# SCHEMATIC.net
KiCad netlist of a schematic drawn in Altium Designer
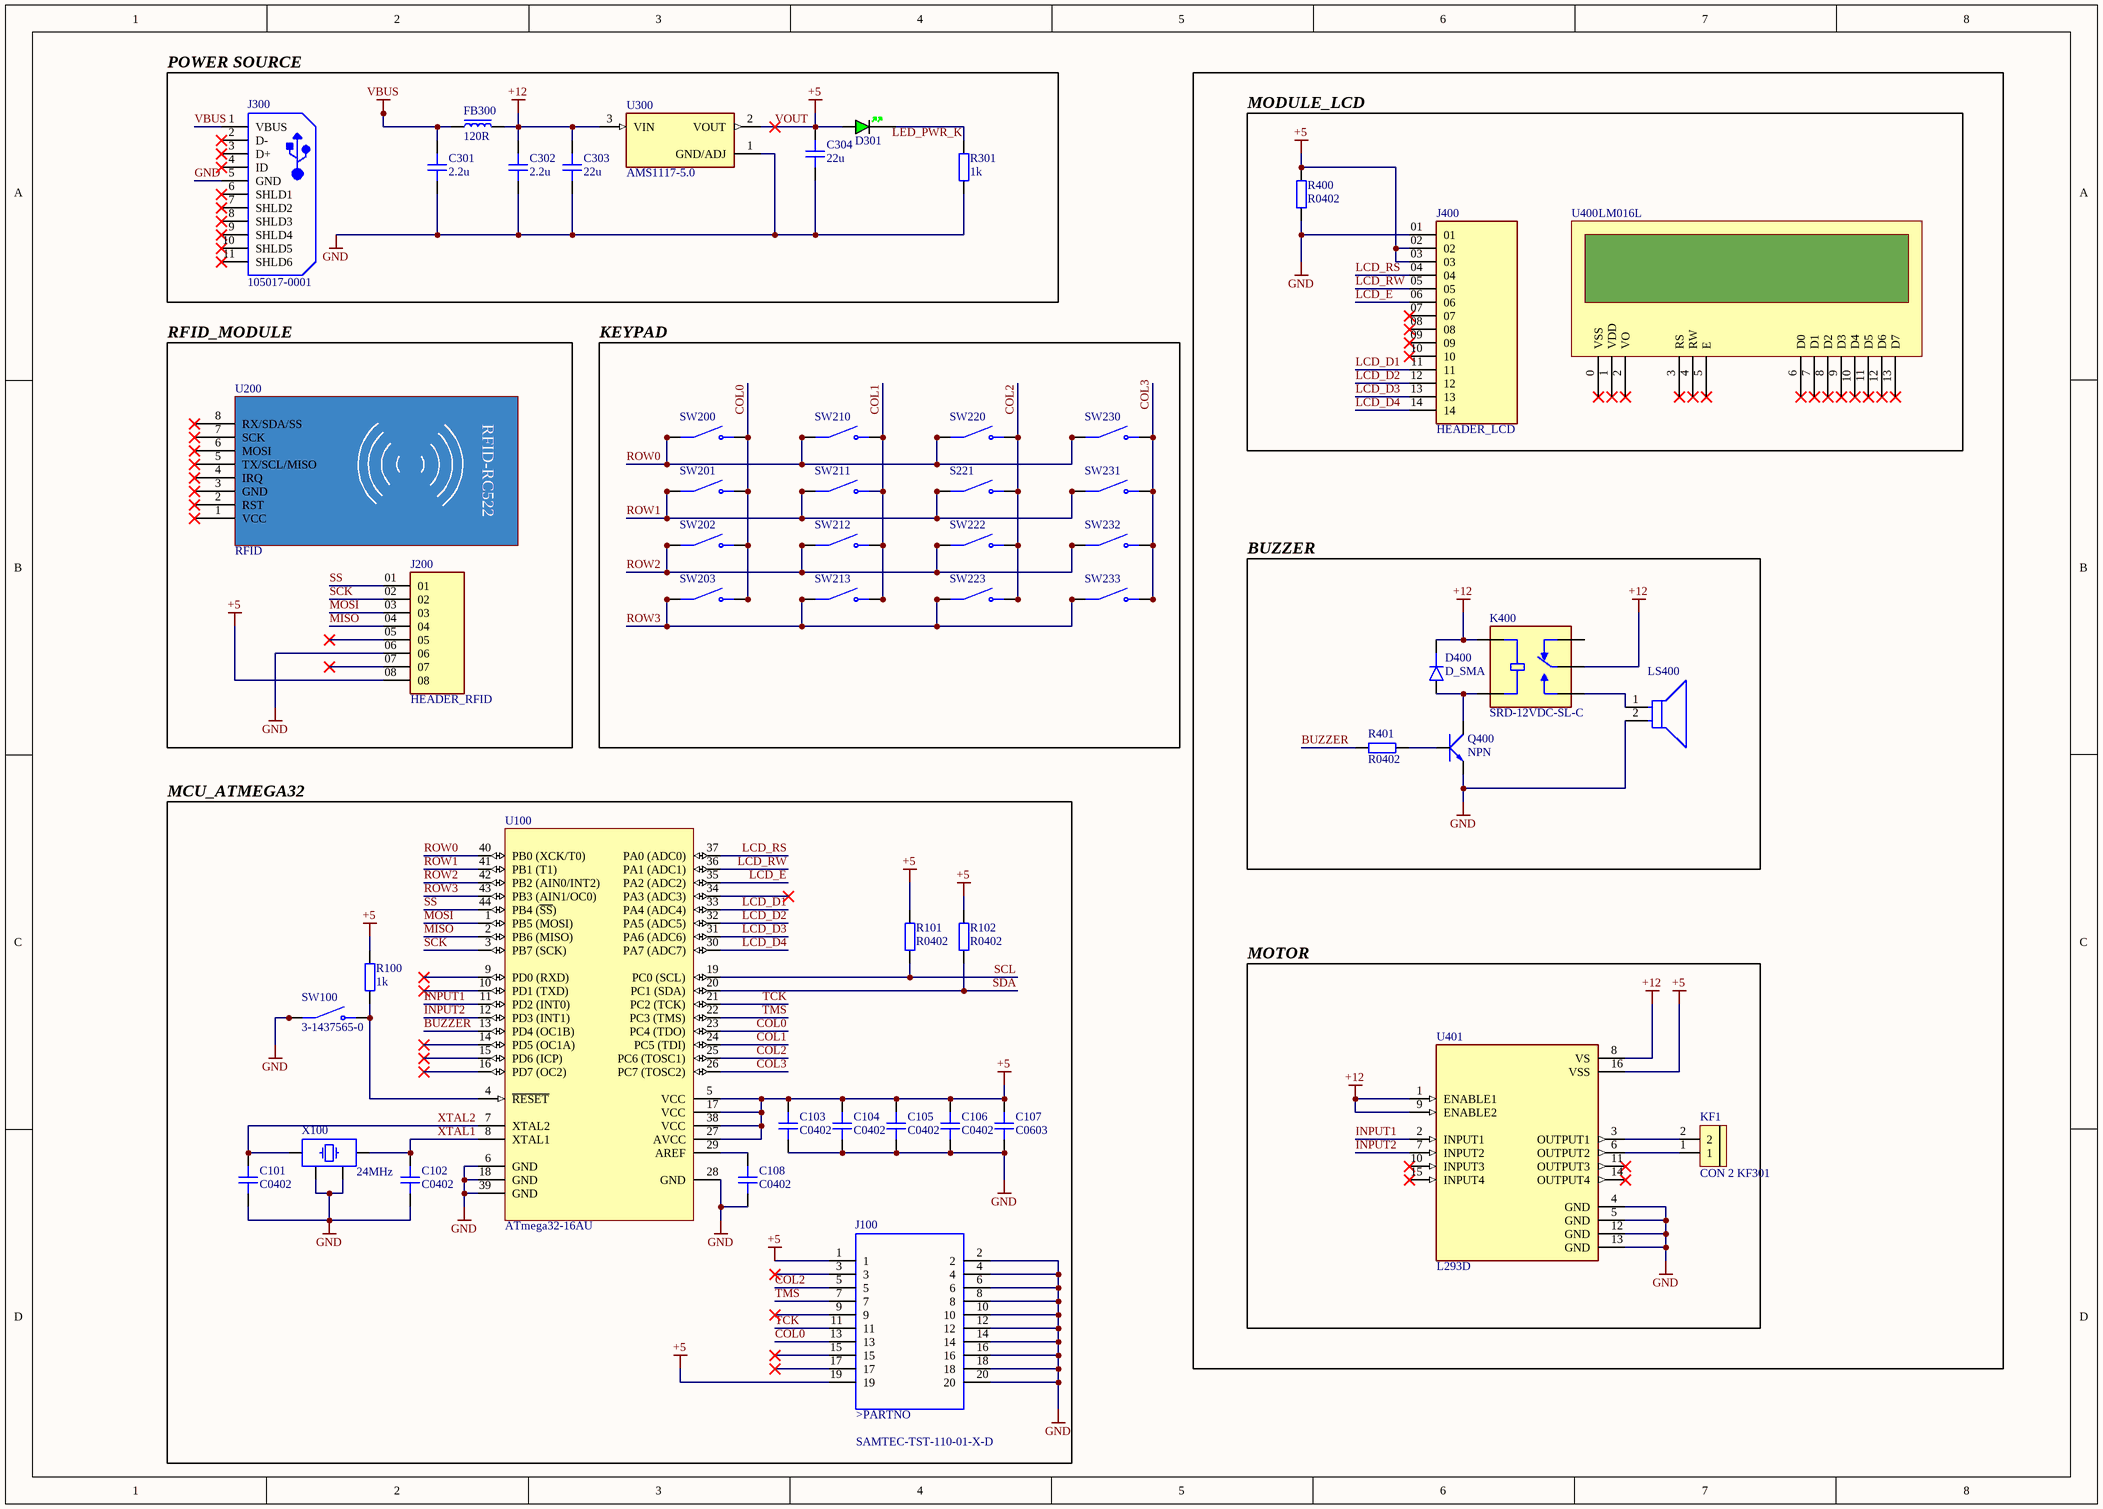
[diagram p0: SCHEMATIC.SchDoc]

(export (version "E")
  (design (tool "Eeschema 10.0.6"))
  (components
    (comp (ref "C101")
      (value "C0402")
      (footprint "CAP_0402")
      (description "Capacitor SMD 0402")
      (libsource (lib "Schematic-Lib-PhilsLab") (part "CAP_0402"))
    )
    (comp (ref "C102")
      (value "C0402")
      (footprint "CAP_0402")
      (description "Capacitor SMD 0402")
      (libsource (lib "Schematic-Lib-PhilsLab") (part "CAP_0402"))
    )
    (comp (ref "C103")
      (value "C0402")
      (footprint "CAP_0402")
      (description "Capacitor SMD 0402")
      (libsource (lib "Schematic-Lib-PhilsLab") (part "CAP_0402"))
    )
    (comp (ref "C104")
      (value "C0402")
      (footprint "CAP_0402")
      (description "Capacitor SMD 0402")
      (libsource (lib "Schematic-Lib-PhilsLab") (part "CAP_0402"))
    )
    (comp (ref "C105")
      (value "C0402")
      (footprint "CAP_0402")
      (description "Capacitor SMD 0402")
      (libsource (lib "Schematic-Lib-PhilsLab") (part "CAP_0402"))
    )
    (comp (ref "C106")
      (value "C0402")
      (footprint "CAP_0402")
      (description "Capacitor SMD 0402")
      (libsource (lib "Schematic-Lib-PhilsLab") (part "CAP_0402"))
    )
    (comp (ref "C107")
      (value "C0603")
      (footprint "CAP_0603")
      (description "Capacitor SMD 0603")
      (libsource (lib "Schematic-Lib-PhilsLab") (part "CAP_0603"))
    )
    (comp (ref "C108")
      (value "C0402")
      (footprint "CAP_0402")
      (description "Capacitor SMD 0402")
      (libsource (lib "Schematic-Lib-PhilsLab") (part "CAP_0402"))
    )
    (comp (ref "C301")
      (value "2.2u")
      (footprint "CAP_0603")
      (description "Capacitor SMD 0603")
      (libsource (lib "Schematic-Lib-PhilsLab") (part "CAP_0603"))
    )
    (comp (ref "C302")
      (value "2.2u")
      (footprint "CAP_0603")
      (description "Capacitor SMD 0603")
      (libsource (lib "Schematic-Lib-PhilsLab") (part "CAP_0603"))
    )
    (comp (ref "C303")
      (value "22u")
      (footprint "CAP_0805")
      (description "Capacitor SMD 0805")
      (libsource (lib "Schematic-Lib-PhilsLab") (part "CAP_0805"))
    )
    (comp (ref "C304")
      (value "22u")
      (footprint "CAP_0805")
      (description "Capacitor SMD 0805")
      (libsource (lib "Schematic-Lib-PhilsLab") (part "CAP_0805"))
    )
    (comp (ref "D301")
      (value "GREEN")
      (footprint "LED_0402_GREEN")
      (description "LED 0402 GREEN SMD")
      (libsource (lib "Schematic-Lib-PhilsLab") (part "LED_0402_GREEN"))
    )
    (comp (ref "D400")
      (value "D_SMA")
      (footprint "DO-214AC-2 (SMA)")
      (description "Diode SMD SMA (DO-214AA)")
      (libsource (lib "Schematic-Lib-PhilsLab") (part "D_SMA"))
    )
    (comp (ref "FB300")
      (value "120R")
      (footprint "FB_0603")
      (description "Ferrite Bead SMD 0603")
      (libsource (lib "Schematic-Lib-PhilsLab") (part "FB_0603"))
    )
    (comp (ref "J100")
      (value "~")
      (footprint "SAMTEC-TST-110-01-X-D")
      (fields (field (name "MF") "Samtec") (field (name "MP") "SAMTEC-TST-110-01-X-D"))
      (libsource (lib "SAMTEC-TST-110-01-X-D") (part "SAMTEC-TST-110-01-X-D"))
    )
    (comp (ref "J200")
      (value "HEADER_RFID")
      (footprint "SAMTEC_TSW-108-X-X-S")
      (description "Connector Header Through Hole 8 position 0.100 (2.54mm)")
      (fields (field (name "MF") "Samtec") (field (name "MP") "TSW-108-23-L-S"))
      (libsource (lib "TSW-108-X-X-S") (part "TSW-108-X-X-S"))
    )
    (comp (ref "J300")
      (value "105017-0001")
      (footprint "USB-MICRO-B_V")
      (fields (field (name "MANUFACTURER") "Molex"))
      (libsource (lib "Altium Content Vault") (part "USB-5-6SHLD"))
    )
    (comp (ref "J400")
      (value "HEADER_LCD")
      (footprint "SAMTEC_TSW-114-07-L-S")
      (description "Connector Header Through Hole 14 position 0.100 (2.54mm)")
      (fields (field (name "MF") "Samtec Inc.") (field (name "MP") "TSW-114-07-L-S"))
      (libsource (lib "TSW-114-07-L-S") (part "TSW-114-07-L-S"))
    )
    (comp (ref "K400")
      (value "SRD-12VDC-SL-C")
      (footprint "RELAY_SRD-12VDC-SL-C")
      (description "General Purpose Non Latching 12VDC SPDT Through Hole Relays RoHS")
      (libsource (lib "SRD-12VDC-SL-C (2)") (part "SRD-12VDC-SL-C"))
    )
    (comp (ref "KF1")
      (value "CON 2 KF301")
      (footprint "Con 2 KF301 5.08")
      (description "Cắm")
      (libsource (lib "Connector") (part "CON 2 KF301"))
    )
    (comp (ref "LS400")
      (value "PKB24SPCH3601-B0")
      (footprint "FP-PKB24SPCH3601-B0-MFG")
      (description "AUDIO PIEZO TRANSDUCER 3-15V TH")
      (libsource (lib "Altium Content Vault") (part "1973c4b650225fd2ddacaff6b763965"))
    )
    (comp (ref "Q400")
      (value "NPN")
      (footprint "TO92")
      (description "NPN transistor EBC")
      (libsource (lib "TranFet") (part "Trans 2N3904"))
    )
    (comp (ref "R100")
      (value "1k")
      (footprint "RES_0402")
      (description "Resistor SMD 0402")
      (libsource (lib "Schematic-Lib-PhilsLab") (part "RES_0402"))
    )
    (comp (ref "R101")
      (value "R0402")
      (footprint "RES_0402")
      (description "Resistor SMD 0402")
      (libsource (lib "Schematic-Lib-PhilsLab") (part "RES_0402"))
    )
    (comp (ref "R102")
      (value "R0402")
      (footprint "RES_0402")
      (description "Resistor SMD 0402")
      (libsource (lib "Schematic-Lib-PhilsLab") (part "RES_0402"))
    )
    (comp (ref "R301")
      (value "1k")
      (footprint "RES_0402")
      (description "Resistor SMD 0402")
      (libsource (lib "Schematic-Lib-PhilsLab") (part "RES_0402"))
    )
    (comp (ref "R400")
      (value "R0402")
      (footprint "RES_0402")
      (description "Resistor SMD 0402")
      (libsource (lib "Schematic-Lib-PhilsLab") (part "RES_0402"))
    )
    (comp (ref "R401")
      (value "R0402")
      (footprint "RES_0402")
      (description "Resistor SMD 0402")
      (libsource (lib "Schematic-Lib-PhilsLab") (part "RES_0402"))
    )
    (comp (ref "S221")
      (value "3-1437565-0")
      (footprint "SW_3-1437565-0")
      (description "Switch Tactile OFF (ON) SPST Round Button Gull Wing 0.05A 24VDC 1VA 9.18N SMD T/R")
      (fields (field (name "MF") "TE Connectivity"))
      (libsource (lib "3-1437565-0") (part "3-1437565-0"))
    )
    (comp (ref "SW100")
      (value "3-1437565-0")
      (footprint "SW_3-1437565-0")
      (description "Switch Tactile OFF (ON) SPST Round Button Gull Wing 0.05A 24VDC 1VA 9.18N SMD T/R")
      (fields (field (name "MF") "TE Connectivity"))
      (libsource (lib "3-1437565-0") (part "3-1437565-0"))
    )
    (comp (ref "SW200")
      (value "3-1437565-0")
      (footprint "SW_3-1437565-0")
      (description "Switch Tactile OFF (ON) SPST Round Button Gull Wing 0.05A 24VDC 1VA 9.18N SMD T/R")
      (fields (field (name "MF") "TE Connectivity"))
      (libsource (lib "3-1437565-0") (part "3-1437565-0"))
    )
    (comp (ref "SW201")
      (value "3-1437565-0")
      (footprint "SW_3-1437565-0")
      (description "Switch Tactile OFF (ON) SPST Round Button Gull Wing 0.05A 24VDC 1VA 9.18N SMD T/R")
      (fields (field (name "MF") "TE Connectivity"))
      (libsource (lib "3-1437565-0") (part "3-1437565-0"))
    )
    (comp (ref "SW202")
      (value "3-1437565-0")
      (footprint "SW_3-1437565-0")
      (description "Switch Tactile OFF (ON) SPST Round Button Gull Wing 0.05A 24VDC 1VA 9.18N SMD T/R")
      (fields (field (name "MF") "TE Connectivity"))
      (libsource (lib "3-1437565-0") (part "3-1437565-0"))
    )
    (comp (ref "SW203")
      (value "3-1437565-0")
      (footprint "SW_3-1437565-0")
      (description "Switch Tactile OFF (ON) SPST Round Button Gull Wing 0.05A 24VDC 1VA 9.18N SMD T/R")
      (fields (field (name "MF") "TE Connectivity"))
      (libsource (lib "3-1437565-0") (part "3-1437565-0"))
    )
    (comp (ref "SW210")
      (value "3-1437565-0")
      (footprint "SW_3-1437565-0")
      (description "Switch Tactile OFF (ON) SPST Round Button Gull Wing 0.05A 24VDC 1VA 9.18N SMD T/R")
      (fields (field (name "MF") "TE Connectivity"))
      (libsource (lib "3-1437565-0") (part "3-1437565-0"))
    )
    (comp (ref "SW211")
      (value "3-1437565-0")
      (footprint "SW_3-1437565-0")
      (description "Switch Tactile OFF (ON) SPST Round Button Gull Wing 0.05A 24VDC 1VA 9.18N SMD T/R")
      (fields (field (name "MF") "TE Connectivity"))
      (libsource (lib "3-1437565-0") (part "3-1437565-0"))
    )
    (comp (ref "SW212")
      (value "3-1437565-0")
      (footprint "SW_3-1437565-0")
      (description "Switch Tactile OFF (ON) SPST Round Button Gull Wing 0.05A 24VDC 1VA 9.18N SMD T/R")
      (fields (field (name "MF") "TE Connectivity"))
      (libsource (lib "3-1437565-0") (part "3-1437565-0"))
    )
    (comp (ref "SW213")
      (value "3-1437565-0")
      (footprint "SW_3-1437565-0")
      (description "Switch Tactile OFF (ON) SPST Round Button Gull Wing 0.05A 24VDC 1VA 9.18N SMD T/R")
      (fields (field (name "MF") "TE Connectivity"))
      (libsource (lib "3-1437565-0") (part "3-1437565-0"))
    )
    (comp (ref "SW220")
      (value "3-1437565-0")
      (footprint "SW_3-1437565-0")
      (description "Switch Tactile OFF (ON) SPST Round Button Gull Wing 0.05A 24VDC 1VA 9.18N SMD T/R")
      (fields (field (name "MF") "TE Connectivity"))
      (libsource (lib "3-1437565-0") (part "3-1437565-0"))
    )
    (comp (ref "SW222")
      (value "3-1437565-0")
      (footprint "SW_3-1437565-0")
      (description "Switch Tactile OFF (ON) SPST Round Button Gull Wing 0.05A 24VDC 1VA 9.18N SMD T/R")
      (fields (field (name "MF") "TE Connectivity"))
      (libsource (lib "3-1437565-0") (part "3-1437565-0"))
    )
    (comp (ref "SW223")
      (value "3-1437565-0")
      (footprint "SW_3-1437565-0")
      (description "Switch Tactile OFF (ON) SPST Round Button Gull Wing 0.05A 24VDC 1VA 9.18N SMD T/R")
      (fields (field (name "MF") "TE Connectivity"))
      (libsource (lib "3-1437565-0") (part "3-1437565-0"))
    )
    (comp (ref "SW230")
      (value "3-1437565-0")
      (footprint "SW_3-1437565-0")
      (description "Switch Tactile OFF (ON) SPST Round Button Gull Wing 0.05A 24VDC 1VA 9.18N SMD T/R")
      (fields (field (name "MF") "TE Connectivity"))
      (libsource (lib "3-1437565-0") (part "3-1437565-0"))
    )
    (comp (ref "SW231")
      (value "3-1437565-0")
      (footprint "SW_3-1437565-0")
      (description "Switch Tactile OFF (ON) SPST Round Button Gull Wing 0.05A 24VDC 1VA 9.18N SMD T/R")
      (fields (field (name "MF") "TE Connectivity"))
      (libsource (lib "3-1437565-0") (part "3-1437565-0"))
    )
    (comp (ref "SW232")
      (value "3-1437565-0")
      (footprint "SW_3-1437565-0")
      (description "Switch Tactile OFF (ON) SPST Round Button Gull Wing 0.05A 24VDC 1VA 9.18N SMD T/R")
      (fields (field (name "MF") "TE Connectivity"))
      (libsource (lib "3-1437565-0") (part "3-1437565-0"))
    )
    (comp (ref "SW233")
      (value "3-1437565-0")
      (footprint "SW_3-1437565-0")
      (description "Switch Tactile OFF (ON) SPST Round Button Gull Wing 0.05A 24VDC 1VA 9.18N SMD T/R")
      (fields (field (name "MF") "TE Connectivity"))
      (libsource (lib "3-1437565-0") (part "3-1437565-0"))
    )
    (comp (ref "U100")
      (value "ATmega32-16AU")
      (footprint "44A_N")
      (libsource (lib "Altium Content Vault") (part "MC-8B-ATM32-SQ44"))
    )
    (comp (ref "U200") (value "RFID") (libsource (lib "RC522") (part "Component_1")))
    (comp (ref "U300")
      (value "AMS1117-5.0")
      (footprint "SOT229P700X180-4N")
      (description "1A LOW DROPOUT VOLTAGE REGULATOR")
      (fields (field (name "MF") "ams"))
      (libsource (lib "AMS1117-5.0") (part "AMS1117-5.0"))
    )
    (comp (ref "U400") (value "LM016L") (libsource (lib "LM016L") (part "LM016L")))
    (comp (ref "U401")
      (value "L293D")
      (footprint "DIP880W50P254L2000H510Q16")
      (description "Bipolar Motor Driver - Parallel 16-PowerDIP")
      (fields (field (name "MF") "STMicroelectronics"))
      (libsource (lib "L293D") (part "L293D"))
    )
    (comp (ref "X100")
      (value "24MHz")
      (footprint "XTAL_3225")
      (description "Crystal SMD 24MHz 10PPM 7pF 3225")
      (fields
        (field (name "MANUFACTURER") "Epson")
        (field (name "MANUFACTURER PART NUMBER") "TSX-3225 24.0000MF15X-AC")
      )
      (libsource (lib "Schematic-Lib-PhilsLab") (part "TSX-3225_24.0000MF15X-AC"))
    )
  )
  (nets
    (net (code "1") (name "+5") (class "Default")
      (node (ref "C103") (pin "2") (pinfunction "2_2") (pintype "passive"))
      (node (ref "C104") (pin "2") (pinfunction "2_2") (pintype "passive"))
      (node (ref "C105") (pin "2") (pinfunction "2_2") (pintype "passive"))
      (node (ref "C106") (pin "2") (pinfunction "2_2") (pintype "passive"))
      (node (ref "C107") (pin "2") (pinfunction "2_2") (pintype "passive"))
      (node (ref "C304") (pin "2") (pinfunction "2_2") (pintype "passive"))
      (node (ref "D301") (pin "A") (pinfunction "A_A") (pintype "passive"))
      (node (ref "J100") (pin "1") (pinfunction "1_1") (pintype "passive"))
      (node (ref "J100") (pin "19") (pinfunction "19_19") (pintype "passive"))
      (node (ref "J200") (pin "08") (pinfunction "08_08") (pintype "passive"))
      (node (ref "J400") (pin "02") (pinfunction "02_02") (pintype "passive"))
      (node (ref "J400") (pin "03") (pinfunction "03_03") (pintype "passive"))
      (node (ref "R100") (pin "2") (pinfunction "2_2") (pintype "passive"))
      (node (ref "R101") (pin "2") (pinfunction "2_2") (pintype "passive"))
      (node (ref "R102") (pin "2") (pinfunction "2_2") (pintype "passive"))
      (node (ref "R400") (pin "2") (pinfunction "2_2") (pintype "passive"))
      (node (ref "U100") (pin "17") (pinfunction "VCC_17") (pintype "power_in"))
      (node (ref "U100") (pin "27") (pinfunction "AVCC_27") (pintype "power_in"))
      (node (ref "U100") (pin "38") (pinfunction "VCC_38") (pintype "power_in"))
      (node (ref "U100") (pin "5") (pinfunction "VCC_5") (pintype "power_in"))
      (node (ref "U300") (pin "2") (pinfunction "VOUT_2") (pintype "output"))
      (node (ref "U401") (pin "16") (pinfunction "VSS_16") (pintype "power_in"))
    )
    (net (code "2") (name "+12") (class "Default")
      (node (ref "C302") (pin "2") (pinfunction "2_2") (pintype "passive"))
      (node (ref "C303") (pin "2") (pinfunction "2_2") (pintype "passive"))
      (node (ref "D400") (pin "K") (pinfunction "K_K") (pintype "passive"))
      (node (ref "FB300") (pin "2") (pinfunction "2_2") (pintype "passive"))
      (node (ref "K400") (pin "COIL1") (pinfunction "COIL1_COIL1") (pintype "passive"))
      (node (ref "K400") (pin "COM") (pinfunction "COM_COM") (pintype "passive"))
      (node (ref "U300") (pin "3") (pinfunction "VIN_3") (pintype "input"))
      (node (ref "U401") (pin "1") (pinfunction "ENABLE1_1") (pintype "input"))
      (node (ref "U401") (pin "8") (pinfunction "VS_8") (pintype "power_in"))
      (node (ref "U401") (pin "9") (pinfunction "ENABLE2_9") (pintype "input"))
    )
    (net (code "3") (name "/BUZZER") (class "Default")
      (node (ref "R401") (pin "1") (pinfunction "1_1") (pintype "passive"))
      (node (ref "U100") (pin "13") (pinfunction "PD4_(OC1B)_13") (pintype "bidirectional"))
    )
    (net (code "4") (name "/COL0") (class "Default")
      (node (ref "J100") (pin "13") (pinfunction "13_13") (pintype "passive"))
      (node (ref "SW200") (pin "3") (pinfunction "NO_3") (pintype "passive"))
      (node (ref "SW200") (pin "4") (pinfunction "NO_4") (pintype "passive"))
      (node (ref "SW201") (pin "3") (pinfunction "NO_3") (pintype "passive"))
      (node (ref "SW201") (pin "4") (pinfunction "NO_4") (pintype "passive"))
      (node (ref "SW202") (pin "3") (pinfunction "NO_3") (pintype "passive"))
      (node (ref "SW202") (pin "4") (pinfunction "NO_4") (pintype "passive"))
      (node (ref "SW203") (pin "3") (pinfunction "NO_3") (pintype "passive"))
      (node (ref "SW203") (pin "4") (pinfunction "NO_4") (pintype "passive"))
      (node (ref "U100") (pin "23") (pinfunction "PC4_(TDO)_23") (pintype "bidirectional"))
    )
    (net (code "5") (name "/COL1") (class "Default")
      (node (ref "SW210") (pin "3") (pinfunction "NO_3") (pintype "passive"))
      (node (ref "SW210") (pin "4") (pinfunction "NO_4") (pintype "passive"))
      (node (ref "SW211") (pin "3") (pinfunction "NO_3") (pintype "passive"))
      (node (ref "SW211") (pin "4") (pinfunction "NO_4") (pintype "passive"))
      (node (ref "SW212") (pin "3") (pinfunction "NO_3") (pintype "passive"))
      (node (ref "SW212") (pin "4") (pinfunction "NO_4") (pintype "passive"))
      (node (ref "SW213") (pin "3") (pinfunction "NO_3") (pintype "passive"))
      (node (ref "SW213") (pin "4") (pinfunction "NO_4") (pintype "passive"))
      (node (ref "U100") (pin "24") (pinfunction "PC5_(TDI)_24") (pintype "bidirectional"))
    )
    (net (code "6") (name "/COL2") (class "Default")
      (node (ref "J100") (pin "5") (pinfunction "5_5") (pintype "passive"))
      (node (ref "S221") (pin "3") (pinfunction "NO_3") (pintype "passive"))
      (node (ref "S221") (pin "4") (pinfunction "NO_4") (pintype "passive"))
      (node (ref "SW220") (pin "3") (pinfunction "NO_3") (pintype "passive"))
      (node (ref "SW220") (pin "4") (pinfunction "NO_4") (pintype "passive"))
      (node (ref "SW222") (pin "3") (pinfunction "NO_3") (pintype "passive"))
      (node (ref "SW222") (pin "4") (pinfunction "NO_4") (pintype "passive"))
      (node (ref "SW223") (pin "3") (pinfunction "NO_3") (pintype "passive"))
      (node (ref "SW223") (pin "4") (pinfunction "NO_4") (pintype "passive"))
      (node (ref "U100") (pin "25") (pinfunction "PC6_(TOSC1)_25") (pintype "bidirectional"))
    )
    (net (code "7") (name "/COL3") (class "Default")
      (node (ref "SW230") (pin "3") (pinfunction "NO_3") (pintype "passive"))
      (node (ref "SW230") (pin "4") (pinfunction "NO_4") (pintype "passive"))
      (node (ref "SW231") (pin "3") (pinfunction "NO_3") (pintype "passive"))
      (node (ref "SW231") (pin "4") (pinfunction "NO_4") (pintype "passive"))
      (node (ref "SW232") (pin "3") (pinfunction "NO_3") (pintype "passive"))
      (node (ref "SW232") (pin "4") (pinfunction "NO_4") (pintype "passive"))
      (node (ref "SW233") (pin "3") (pinfunction "NO_3") (pintype "passive"))
      (node (ref "SW233") (pin "4") (pinfunction "NO_4") (pintype "passive"))
      (node (ref "U100") (pin "26") (pinfunction "PC7_(TOSC2)_26") (pintype "bidirectional"))
    )
    (net (code "8") (name "/INPUT1") (class "Default")
      (node (ref "U100") (pin "11") (pinfunction "PD2_(INT0)_11") (pintype "bidirectional"))
      (node (ref "U401") (pin "2") (pinfunction "INPUT1_2") (pintype "input"))
    )
    (net (code "9") (name "/INPUT2") (class "Default")
      (node (ref "U100") (pin "12") (pinfunction "PD3_(INT1)_12") (pintype "bidirectional"))
      (node (ref "U401") (pin "7") (pinfunction "INPUT2_7") (pintype "input"))
    )
    (net (code "10") (name "/LCD_D1") (class "Default")
      (node (ref "J400") (pin "11") (pinfunction "11_11") (pintype "passive"))
      (node (ref "U100") (pin "33") (pinfunction "PA4_(ADC4)_33") (pintype "bidirectional"))
    )
    (net (code "11") (name "/LCD_D2") (class "Default")
      (node (ref "J400") (pin "12") (pinfunction "12_12") (pintype "passive"))
      (node (ref "U100") (pin "32") (pinfunction "PA5_(ADC5)_32") (pintype "bidirectional"))
    )
    (net (code "12") (name "/LCD_D3") (class "Default")
      (node (ref "J400") (pin "13") (pinfunction "13_13") (pintype "passive"))
      (node (ref "U100") (pin "31") (pinfunction "PA6_(ADC6)_31") (pintype "bidirectional"))
    )
    (net (code "13") (name "/LCD_D4") (class "Default")
      (node (ref "J400") (pin "14") (pinfunction "14_14") (pintype "passive"))
      (node (ref "U100") (pin "30") (pinfunction "PA7_(ADC7)_30") (pintype "bidirectional"))
    )
    (net (code "14") (name "/LCD_E") (class "Default")
      (node (ref "J400") (pin "06") (pinfunction "06_06") (pintype "passive"))
      (node (ref "U100") (pin "35") (pinfunction "PA2_(ADC2)_35") (pintype "bidirectional"))
    )
    (net (code "15") (name "/LCD_RS") (class "Default")
      (node (ref "J400") (pin "04") (pinfunction "04_04") (pintype "passive"))
      (node (ref "U100") (pin "37") (pinfunction "PA0_(ADC0)_37") (pintype "bidirectional"))
    )
    (net (code "16") (name "/LCD_RW") (class "Default")
      (node (ref "J400") (pin "05") (pinfunction "05_05") (pintype "passive"))
      (node (ref "U100") (pin "36") (pinfunction "PA1_(ADC1)_36") (pintype "bidirectional"))
    )
    (net (code "17") (name "/LED_PWR_K") (class "Default")
      (node (ref "D301") (pin "K") (pinfunction "K_K") (pintype "passive"))
      (node (ref "R301") (pin "2") (pinfunction "2_2") (pintype "passive"))
    )
    (net (code "18") (name "/MISO") (class "Default")
      (node (ref "J200") (pin "04") (pinfunction "04_04") (pintype "passive"))
      (node (ref "U100") (pin "2") (pinfunction "PB6_(MISO)_2") (pintype "bidirectional"))
    )
    (net (code "19") (name "/MOSI") (class "Default")
      (node (ref "J200") (pin "03") (pinfunction "03_03") (pintype "passive"))
      (node (ref "U100") (pin "1") (pinfunction "PB5_(MOSI)_1") (pintype "bidirectional"))
    )
    (net (code "20") (name "/ROW0") (class "Default")
      (node (ref "SW200") (pin "1") (pinfunction "COM_1") (pintype "passive"))
      (node (ref "SW200") (pin "2") (pinfunction "COM_2") (pintype "passive"))
      (node (ref "SW210") (pin "1") (pinfunction "COM_1") (pintype "passive"))
      (node (ref "SW210") (pin "2") (pinfunction "COM_2") (pintype "passive"))
      (node (ref "SW220") (pin "1") (pinfunction "COM_1") (pintype "passive"))
      (node (ref "SW220") (pin "2") (pinfunction "COM_2") (pintype "passive"))
      (node (ref "SW230") (pin "1") (pinfunction "COM_1") (pintype "passive"))
      (node (ref "SW230") (pin "2") (pinfunction "COM_2") (pintype "passive"))
      (node (ref "U100") (pin "40") (pinfunction "PB0_(XCK/T0)_40") (pintype "bidirectional"))
    )
    (net (code "21") (name "/ROW1") (class "Default")
      (node (ref "S221") (pin "1") (pinfunction "COM_1") (pintype "passive"))
      (node (ref "S221") (pin "2") (pinfunction "COM_2") (pintype "passive"))
      (node (ref "SW201") (pin "1") (pinfunction "COM_1") (pintype "passive"))
      (node (ref "SW201") (pin "2") (pinfunction "COM_2") (pintype "passive"))
      (node (ref "SW211") (pin "1") (pinfunction "COM_1") (pintype "passive"))
      (node (ref "SW211") (pin "2") (pinfunction "COM_2") (pintype "passive"))
      (node (ref "SW231") (pin "1") (pinfunction "COM_1") (pintype "passive"))
      (node (ref "SW231") (pin "2") (pinfunction "COM_2") (pintype "passive"))
      (node (ref "U100") (pin "41") (pinfunction "PB1_(T1)_41") (pintype "bidirectional"))
    )
    (net (code "22") (name "/ROW2") (class "Default")
      (node (ref "SW202") (pin "1") (pinfunction "COM_1") (pintype "passive"))
      (node (ref "SW202") (pin "2") (pinfunction "COM_2") (pintype "passive"))
      (node (ref "SW212") (pin "1") (pinfunction "COM_1") (pintype "passive"))
      (node (ref "SW212") (pin "2") (pinfunction "COM_2") (pintype "passive"))
      (node (ref "SW222") (pin "1") (pinfunction "COM_1") (pintype "passive"))
      (node (ref "SW222") (pin "2") (pinfunction "COM_2") (pintype "passive"))
      (node (ref "SW232") (pin "1") (pinfunction "COM_1") (pintype "passive"))
      (node (ref "SW232") (pin "2") (pinfunction "COM_2") (pintype "passive"))
      (node (ref "U100") (pin "42") (pinfunction "PB2_(AIN0/INT2)_42") (pintype "bidirectional"))
    )
    (net (code "23") (name "/ROW3") (class "Default")
      (node (ref "SW203") (pin "1") (pinfunction "COM_1") (pintype "passive"))
      (node (ref "SW203") (pin "2") (pinfunction "COM_2") (pintype "passive"))
      (node (ref "SW213") (pin "1") (pinfunction "COM_1") (pintype "passive"))
      (node (ref "SW213") (pin "2") (pinfunction "COM_2") (pintype "passive"))
      (node (ref "SW223") (pin "1") (pinfunction "COM_1") (pintype "passive"))
      (node (ref "SW223") (pin "2") (pinfunction "COM_2") (pintype "passive"))
      (node (ref "SW233") (pin "1") (pinfunction "COM_1") (pintype "passive"))
      (node (ref "SW233") (pin "2") (pinfunction "COM_2") (pintype "passive"))
      (node (ref "U100") (pin "43") (pinfunction "PB3_(AIN1/OC0)_43") (pintype "bidirectional"))
    )
    (net (code "24") (name "/SCK") (class "Default")
      (node (ref "J200") (pin "02") (pinfunction "02_02") (pintype "passive"))
      (node (ref "U100") (pin "3") (pinfunction "PB7_(SCK)_3") (pintype "bidirectional"))
    )
    (net (code "25") (name "/SCL") (class "Default")
      (node (ref "R101") (pin "1") (pinfunction "1_1") (pintype "passive"))
      (node (ref "U100") (pin "19") (pinfunction "PC0_(SCL)_19") (pintype "bidirectional"))
    )
    (net (code "26") (name "/SDA") (class "Default")
      (node (ref "R102") (pin "1") (pinfunction "1_1") (pintype "passive"))
      (node (ref "U100") (pin "20") (pinfunction "PC1_(SDA)_20") (pintype "bidirectional"))
    )
    (net (code "27") (name "/SS") (class "Default")
      (node (ref "J200") (pin "01") (pinfunction "01_01") (pintype "passive"))
      (node (ref "U100") (pin "44") (pinfunction "PB4_(~{SS})_44") (pintype "bidirectional"))
    )
    (net (code "28") (name "/TCK") (class "Default")
      (node (ref "J100") (pin "11") (pinfunction "11_11") (pintype "passive"))
      (node (ref "U100") (pin "21") (pinfunction "PC2_(TCK)_21") (pintype "bidirectional"))
    )
    (net (code "29") (name "/TMS") (class "Default")
      (node (ref "J100") (pin "7") (pinfunction "7_7") (pintype "passive"))
      (node (ref "U100") (pin "22") (pinfunction "PC3_(TMS)_22") (pintype "bidirectional"))
    )
    (net (code "31") (name "/XTAL1") (class "Default")
      (node (ref "C102") (pin "2") (pinfunction "2_2") (pintype "passive"))
      (node (ref "U100") (pin "8") (pinfunction "XTAL1_8") (pintype "passive"))
      (node (ref "X100") (pin "3") (pinfunction "3_3") (pintype "passive"))
    )
    (net (code "32") (name "/XTAL2") (class "Default")
      (node (ref "C101") (pin "2") (pinfunction "2_2") (pintype "passive"))
      (node (ref "U100") (pin "7") (pinfunction "XTAL2_7") (pintype "passive"))
      (node (ref "X100") (pin "1") (pinfunction "1_1") (pintype "passive"))
    )
    (net (code "33") (name "GND") (class "Default")
      (node (ref "C101") (pin "1") (pinfunction "1_1") (pintype "passive"))
      (node (ref "C102") (pin "1") (pinfunction "1_1") (pintype "passive"))
      (node (ref "C103") (pin "1") (pinfunction "1_1") (pintype "passive"))
      (node (ref "C104") (pin "1") (pinfunction "1_1") (pintype "passive"))
      (node (ref "C105") (pin "1") (pinfunction "1_1") (pintype "passive"))
      (node (ref "C106") (pin "1") (pinfunction "1_1") (pintype "passive"))
      (node (ref "C107") (pin "1") (pinfunction "1_1") (pintype "passive"))
      (node (ref "C108") (pin "1") (pinfunction "1_1") (pintype "passive"))
      (node (ref "C301") (pin "1") (pinfunction "1_1") (pintype "passive"))
      (node (ref "C302") (pin "1") (pinfunction "1_1") (pintype "passive"))
      (node (ref "C303") (pin "1") (pinfunction "1_1") (pintype "passive"))
      (node (ref "C304") (pin "1") (pinfunction "1_1") (pintype "passive"))
      (node (ref "J100") (pin "10") (pinfunction "10_10") (pintype "passive"))
      (node (ref "J100") (pin "12") (pinfunction "12_12") (pintype "passive"))
      (node (ref "J100") (pin "14") (pinfunction "14_14") (pintype "passive"))
      (node (ref "J100") (pin "16") (pinfunction "16_16") (pintype "passive"))
      (node (ref "J100") (pin "18") (pinfunction "18_18") (pintype "passive"))
      (node (ref "J100") (pin "2") (pinfunction "2_2") (pintype "passive"))
      (node (ref "J100") (pin "20") (pinfunction "20_20") (pintype "passive"))
      (node (ref "J100") (pin "4") (pinfunction "4_4") (pintype "passive"))
      (node (ref "J100") (pin "6") (pinfunction "6_6") (pintype "passive"))
      (node (ref "J100") (pin "8") (pinfunction "8_8") (pintype "passive"))
      (node (ref "J200") (pin "06") (pinfunction "06_06") (pintype "passive"))
      (node (ref "J300") (pin "5") (pinfunction "GND_5") (pintype "passive"))
      (node (ref "J400") (pin "01") (pinfunction "01_01") (pintype "passive"))
      (node (ref "LS400") (pin "2") (pinfunction "A_2") (pintype "passive"))
      (node (ref "Q400") (pin "1") (pinfunction "E_1") (pintype "passive"))
      (node (ref "R301") (pin "1") (pinfunction "1_1") (pintype "passive"))
      (node (ref "R400") (pin "1") (pinfunction "1_1") (pintype "passive"))
      (node (ref "SW100") (pin "1") (pinfunction "COM_1") (pintype "passive"))
      (node (ref "SW100") (pin "2") (pinfunction "COM_2") (pintype "passive"))
      (node (ref "U100") (pin "18") (pinfunction "GND_18") (pintype "power_in"))
      (node (ref "U100") (pin "28") (pinfunction "GND_28") (pintype "power_in"))
      (node (ref "U100") (pin "39") (pinfunction "GND_39") (pintype "power_in"))
      (node (ref "U100") (pin "6") (pinfunction "GND_6") (pintype "power_in"))
      (node (ref "U300") (pin "1") (pinfunction "GND/ADJ_1") (pintype "power_in"))
      (node (ref "U401") (pin "12") (pinfunction "GND_12") (pintype "power_in"))
      (node (ref "U401") (pin "13") (pinfunction "GND_13") (pintype "power_in"))
      (node (ref "U401") (pin "4") (pinfunction "GND_4") (pintype "power_in"))
      (node (ref "U401") (pin "5") (pinfunction "GND_5") (pintype "power_in"))
      (node (ref "X100") (pin "2") (pinfunction "2_2") (pintype "passive"))
      (node (ref "X100") (pin "4") (pinfunction "4_4") (pintype "passive"))
    )
    (net (code "34") (name "Net-(LS400-C)") (class "Default")
      (node (ref "K400") (pin "NO") (pinfunction "NO_NO") (pintype "passive"))
      (node (ref "LS400") (pin "1") (pinfunction "C_1") (pintype "passive"))
    )
    (net (code "35") (name "Net-(Q400-B)") (class "Default")
      (node (ref "Q400") (pin "2") (pinfunction "B_2") (pintype "passive"))
      (node (ref "R401") (pin "2") (pinfunction "2_2") (pintype "passive"))
    )
    (net (code "36") (name "Net-(Q400-C)") (class "Default")
      (node (ref "D400") (pin "A") (pinfunction "A_A") (pintype "passive"))
      (node (ref "K400") (pin "COIL2") (pinfunction "COIL2_COIL2") (pintype "passive"))
      (node (ref "Q400") (pin "3") (pinfunction "C_3") (pintype "passive"))
    )
    (net (code "37") (name "Net-(U100-AREF)") (class "Default")
      (node (ref "C108") (pin "2") (pinfunction "2_2") (pintype "passive"))
      (node (ref "U100") (pin "29") (pinfunction "AREF_29") (pintype "passive"))
    )
    (net (code "38") (name "Net-(U100-~{RESET})") (class "Default")
      (node (ref "R100") (pin "1") (pinfunction "1_1") (pintype "passive"))
      (node (ref "SW100") (pin "3") (pinfunction "NO_3") (pintype "passive"))
      (node (ref "SW100") (pin "4") (pinfunction "NO_4") (pintype "passive"))
      (node (ref "U100") (pin "4") (pinfunction "~{RESET}_4") (pintype "input"))
    )
    (net (code "39") (name "Net-(U401-OUTPUT1)") (class "Default")
      (node (ref "KF1") (pin "2") (pinfunction "2_2") (pintype "passive"))
      (node (ref "U401") (pin "3") (pinfunction "OUTPUT1_3") (pintype "output"))
    )
    (net (code "40") (name "Net-(U401-OUTPUT2)") (class "Default")
      (node (ref "KF1") (pin "1") (pinfunction "1_1") (pintype "passive"))
      (node (ref "U401") (pin "6") (pinfunction "OUTPUT2_6") (pintype "output"))
    )
    (net (code "41") (name "VBUS") (class "Default")
      (node (ref "C301") (pin "2") (pinfunction "2_2") (pintype "passive"))
      (node (ref "FB300") (pin "1") (pinfunction "1_1") (pintype "passive"))
      (node (ref "J300") (pin "1") (pinfunction "VBUS_1") (pintype "passive"))
    )
    (net (code "42") (name "unconnected-(J100-Pad3)") (class "Default")
      (node (ref "J100") (pin "3") (pinfunction "3_3") (pintype "passive+no_connect"))
    )
    (net (code "43") (name "unconnected-(J100-Pad9)") (class "Default")
      (node (ref "J100") (pin "9") (pinfunction "9_9") (pintype "passive+no_connect"))
    )
    (net (code "44") (name "unconnected-(J100-Pad15)") (class "Default")
      (node (ref "J100") (pin "15") (pinfunction "15_15") (pintype "passive+no_connect"))
    )
    (net (code "45") (name "unconnected-(J100-Pad17)") (class "Default")
      (node (ref "J100") (pin "17") (pinfunction "17_17") (pintype "passive+no_connect"))
    )
    (net (code "46") (name "unconnected-(J200-Pad05)") (class "Default")
      (node (ref "J200") (pin "05") (pinfunction "05_05") (pintype "passive+no_connect"))
    )
    (net (code "47") (name "unconnected-(J200-Pad07)") (class "Default")
      (node (ref "J200") (pin "07") (pinfunction "07_07") (pintype "passive+no_connect"))
    )
    (net (code "48") (name "unconnected-(J300-D+-Pad3)") (class "Default")
      (node (ref "J300") (pin "3") (pinfunction "D+_3") (pintype "passive+no_connect"))
    )
    (net (code "49") (name "unconnected-(J300-D--Pad2)") (class "Default")
      (node (ref "J300") (pin "2") (pinfunction "D-_2") (pintype "passive+no_connect"))
    )
    (net (code "50") (name "unconnected-(J300-ID-Pad4)") (class "Default")
      (node (ref "J300") (pin "4") (pinfunction "ID_4") (pintype "passive+no_connect"))
    )
    (net (code "51") (name "unconnected-(J300-SHLD1-Pad6)") (class "Default")
      (node (ref "J300") (pin "6") (pinfunction "SHLD1_6") (pintype "passive+no_connect"))
    )
    (net (code "52") (name "unconnected-(J300-SHLD2-Pad7)") (class "Default")
      (node (ref "J300") (pin "7") (pinfunction "SHLD2_7") (pintype "passive+no_connect"))
    )
    (net (code "53") (name "unconnected-(J300-SHLD3-Pad8)") (class "Default")
      (node (ref "J300") (pin "8") (pinfunction "SHLD3_8") (pintype "passive+no_connect"))
    )
    (net (code "54") (name "unconnected-(J300-SHLD4-Pad9)") (class "Default")
      (node (ref "J300") (pin "9") (pinfunction "SHLD4_9") (pintype "passive+no_connect"))
    )
    (net (code "55") (name "unconnected-(J300-SHLD5-Pad10)") (class "Default")
      (node (ref "J300") (pin "10") (pinfunction "SHLD5_10") (pintype "passive+no_connect"))
    )
    (net (code "56") (name "unconnected-(J300-SHLD6-Pad11)") (class "Default")
      (node (ref "J300") (pin "11") (pinfunction "SHLD6_11") (pintype "passive+no_connect"))
    )
    (net (code "57") (name "unconnected-(J400-Pad07)") (class "Default")
      (node (ref "J400") (pin "07") (pinfunction "07_07") (pintype "passive+no_connect"))
    )
    (net (code "58") (name "unconnected-(J400-Pad08)") (class "Default")
      (node (ref "J400") (pin "08") (pinfunction "08_08") (pintype "passive+no_connect"))
    )
    (net (code "59") (name "unconnected-(J400-Pad09)") (class "Default")
      (node (ref "J400") (pin "09") (pinfunction "09_09") (pintype "passive+no_connect"))
    )
    (net (code "60") (name "unconnected-(J400-Pad10)") (class "Default")
      (node (ref "J400") (pin "10") (pinfunction "10_10") (pintype "passive+no_connect"))
    )
    (net (code "61") (name "unconnected-(K400-PadNC)") (class "Default")
      (node (ref "K400") (pin "NC") (pinfunction "NC_NC") (pintype "passive"))
    )
    (net (code "62") (name "unconnected-(U100-PA3_(ADC3)-Pad34)") (class "Default")
      (node (ref "U100") (pin "34") (pinfunction "PA3_(ADC3)_34") (pintype "bidirectional+no_connect"))
    )
    (net (code "63") (name "unconnected-(U100-PD0_(RXD)-Pad9)") (class "Default")
      (node (ref "U100") (pin "9") (pinfunction "PD0_(RXD)_9") (pintype "bidirectional+no_connect"))
    )
    (net (code "64") (name "unconnected-(U100-PD1_(TXD)-Pad10)") (class "Default")
      (node (ref "U100") (pin "10") (pinfunction "PD1_(TXD)_10") (pintype "bidirectional+no_connect"))
    )
    (net (code "65") (name "unconnected-(U100-PD5_(OC1A)-Pad14)") (class "Default")
      (node (ref "U100") (pin "14") (pinfunction "PD5_(OC1A)_14") (pintype "bidirectional+no_connect"))
    )
    (net (code "66") (name "unconnected-(U100-PD6_(ICP)-Pad15)") (class "Default")
      (node (ref "U100") (pin "15") (pinfunction "PD6_(ICP)_15") (pintype "bidirectional+no_connect"))
    )
    (net (code "67") (name "unconnected-(U100-PD7_(OC2)-Pad16)") (class "Default")
      (node (ref "U100") (pin "16") (pinfunction "PD7_(OC2)_16") (pintype "bidirectional+no_connect"))
    )
    (net (code "68") (name "unconnected-(U200-GND-Pad3)") (class "Default")
      (node (ref "U200") (pin "3") (pinfunction "GND_3") (pintype "passive+no_connect"))
    )
    (net (code "69") (name "unconnected-(U200-IRQ-Pad4)") (class "Default")
      (node (ref "U200") (pin "4") (pinfunction "IRQ_4") (pintype "passive+no_connect"))
    )
    (net (code "70") (name "unconnected-(U200-MOSI-Pad6)") (class "Default")
      (node (ref "U200") (pin "6") (pinfunction "MOSI_6") (pintype "passive+no_connect"))
    )
    (net (code "71") (name "unconnected-(U200-RST-Pad2)") (class "Default")
      (node (ref "U200") (pin "2") (pinfunction "RST_2") (pintype "passive+no_connect"))
    )
    (net (code "72") (name "unconnected-(U200-RX{slash}SDA{slash}SS-Pad8)") (class "Default")
      (node (ref "U200") (pin "8") (pinfunction "RX/SDA/SS_8") (pintype "passive+no_connect"))
    )
    (net (code "73") (name "unconnected-(U200-SCK-Pad7)") (class "Default")
      (node (ref "U200") (pin "7") (pinfunction "SCK_7") (pintype "passive+no_connect"))
    )
    (net (code "74") (name "unconnected-(U200-TX{slash}SCL{slash}MISO-Pad5)") (class "Default")
      (node (ref "U200") (pin "5") (pinfunction "TX/SCL/MISO_5") (pintype "passive+no_connect"))
    )
    (net (code "75") (name "unconnected-(U200-VCC-Pad1)") (class "Default")
      (node (ref "U200") (pin "1") (pinfunction "VCC_1") (pintype "passive+no_connect"))
    )
    (net (code "76") (name "unconnected-(U400-D0-Pad6)") (class "Default")
      (node (ref "U400") (pin "6") (pinfunction "D0_6") (pintype "passive+no_connect"))
    )
    (net (code "77") (name "unconnected-(U400-D1-Pad7)") (class "Default")
      (node (ref "U400") (pin "7") (pinfunction "D1_7") (pintype "passive+no_connect"))
    )
    (net (code "78") (name "unconnected-(U400-D2-Pad8)") (class "Default")
      (node (ref "U400") (pin "8") (pinfunction "D2_8") (pintype "passive+no_connect"))
    )
    (net (code "79") (name "unconnected-(U400-D3-Pad9)") (class "Default")
      (node (ref "U400") (pin "9") (pinfunction "D3_9") (pintype "passive+no_connect"))
    )
    (net (code "80") (name "unconnected-(U400-D4-Pad10)") (class "Default")
      (node (ref "U400") (pin "10") (pinfunction "D4_10") (pintype "passive+no_connect"))
    )
    (net (code "81") (name "unconnected-(U400-D5-Pad11)") (class "Default")
      (node (ref "U400") (pin "11") (pinfunction "D5_11") (pintype "passive+no_connect"))
    )
    (net (code "82") (name "unconnected-(U400-D6-Pad12)") (class "Default")
      (node (ref "U400") (pin "12") (pinfunction "D6_12") (pintype "passive+no_connect"))
    )
    (net (code "83") (name "unconnected-(U400-D7-Pad13)") (class "Default")
      (node (ref "U400") (pin "13") (pinfunction "D7_13") (pintype "passive+no_connect"))
    )
    (net (code "84") (name "unconnected-(U400-E-Pad5)") (class "Default")
      (node (ref "U400") (pin "5") (pinfunction "E_5") (pintype "passive+no_connect"))
    )
    (net (code "85") (name "unconnected-(U400-RS-Pad3)") (class "Default")
      (node (ref "U400") (pin "3") (pinfunction "RS_3") (pintype "passive+no_connect"))
    )
    (net (code "86") (name "unconnected-(U400-RW-Pad4)") (class "Default")
      (node (ref "U400") (pin "4") (pinfunction "RW_4") (pintype "passive+no_connect"))
    )
    (net (code "87") (name "unconnected-(U400-VDD-Pad1)") (class "Default")
      (node (ref "U400") (pin "1") (pinfunction "VDD_1") (pintype "passive+no_connect"))
    )
    (net (code "88") (name "unconnected-(U400-VO-Pad2)") (class "Default")
      (node (ref "U400") (pin "2") (pinfunction "VO_2") (pintype "passive+no_connect"))
    )
    (net (code "89") (name "unconnected-(U400-VSS-Pad0)") (class "Default")
      (node (ref "U400") (pin "0") (pinfunction "VSS_0") (pintype "passive+no_connect"))
    )
    (net (code "90") (name "unconnected-(U401-INPUT3-Pad10)") (class "Default")
      (node (ref "U401") (pin "10") (pinfunction "INPUT3_10") (pintype "input+no_connect"))
    )
    (net (code "91") (name "unconnected-(U401-INPUT4-Pad15)") (class "Default")
      (node (ref "U401") (pin "15") (pinfunction "INPUT4_15") (pintype "input+no_connect"))
    )
    (net (code "92") (name "unconnected-(U401-OUTPUT3-Pad11)") (class "Default")
      (node (ref "U401") (pin "11") (pinfunction "OUTPUT3_11") (pintype "output+no_connect"))
    )
    (net (code "93") (name "unconnected-(U401-OUTPUT4-Pad14)") (class "Default")
      (node (ref "U401") (pin "14") (pinfunction "OUTPUT4_14") (pintype "output+no_connect"))
    )
  )
)
